# lightplayslider.net
KiCad netlist of a schematic drawn in EAGLE
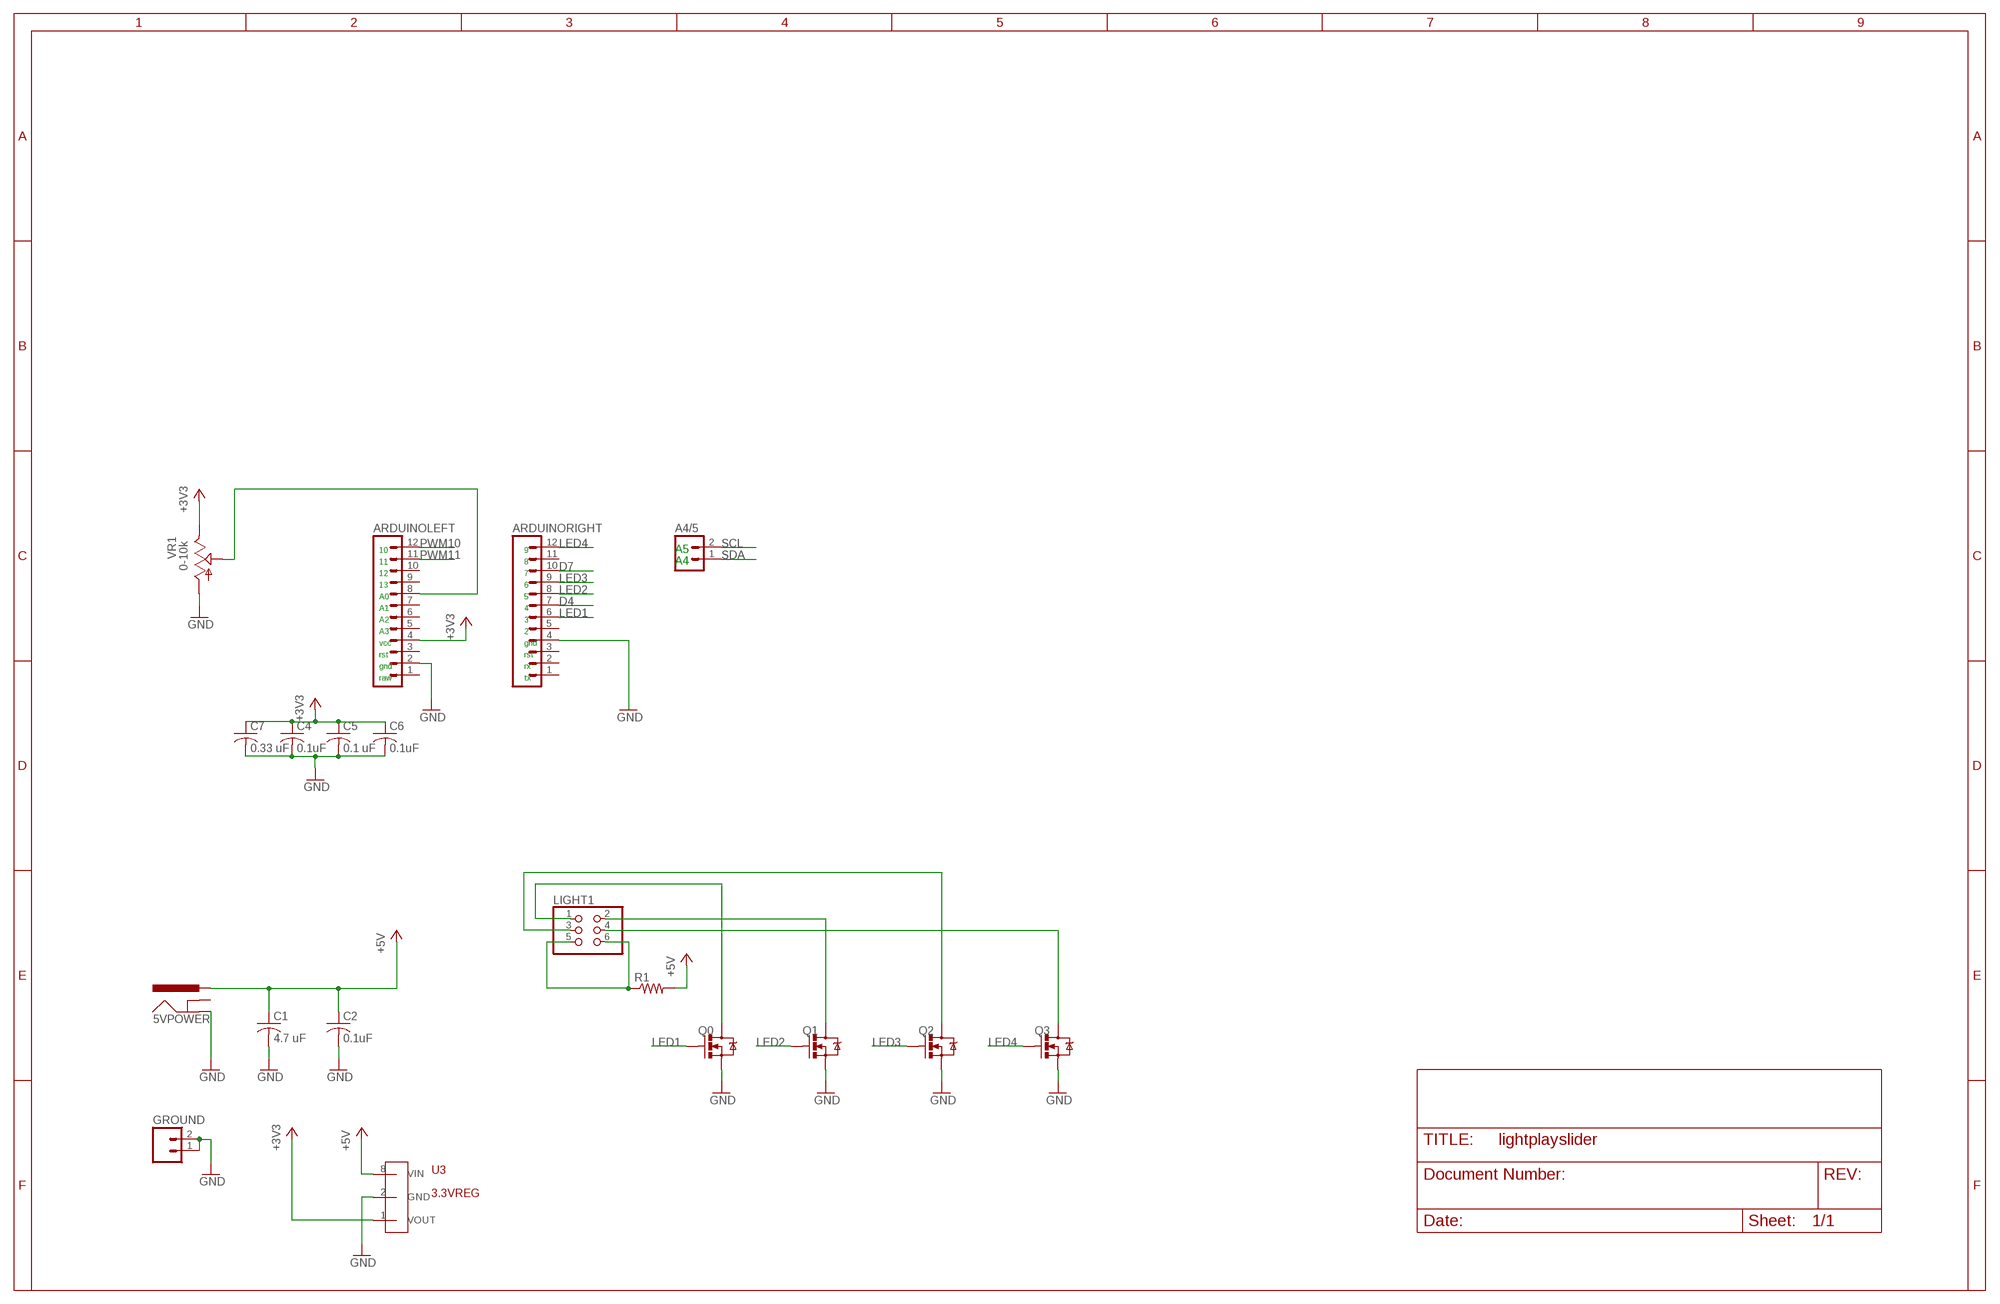
[diagram p0: schematic, sheet 1]

(export (version "E")
  (design (tool "Eeschema 10.0.6"))
  (components
    (comp (ref "5VPOWER")
      (value "POWER_JACKPTH")
      (footprint "eagle-import:POWER_JACK_PTH")
      (libsource (lib "eagle-import") (part "POWER_JACKPTH"))
    )
    (comp (ref "A4/5")
      (value "M02PTH")
      (footprint "eagle-import:1X02")
      (libsource (lib "eagle-import") (part "M02PTH"))
    )
    (comp (ref "ARDUINOLEFT")
      (value "M12PTH")
      (footprint "eagle-import:1X12")
      (libsource (lib "eagle-import") (part "M12PTH"))
    )
    (comp (ref "ARDUINORIGHT")
      (value "M12PTH")
      (footprint "eagle-import:1X12")
      (libsource (lib "eagle-import") (part "M12PTH"))
    )
    (comp (ref "C1")
      (value "4.7 uF")
      (footprint "eagle-import:C1206")
      (libsource (lib "eagle-import") (part "C-USC1206"))
    )
    (comp (ref "C2")
      (value "0.1uF")
      (footprint "eagle-import:C0805")
      (libsource (lib "eagle-import") (part "C-USC0805"))
    )
    (comp (ref "C4")
      (value "0.1uF")
      (footprint "eagle-import:C0805")
      (libsource (lib "eagle-import") (part "C-USC0805"))
    )
    (comp (ref "C5")
      (value "0.1 uF")
      (footprint "eagle-import:C0805")
      (libsource (lib "eagle-import") (part "C-USC0805"))
    )
    (comp (ref "C6")
      (value "0.1uF")
      (footprint "eagle-import:C0805")
      (libsource (lib "eagle-import") (part "C-USC0805"))
    )
    (comp (ref "C7")
      (value "0.33 uF")
      (footprint "eagle-import:C1206")
      (libsource (lib "eagle-import") (part "C-USC1206"))
    )
    (comp (ref "GROUND")
      (value "M02PTH")
      (footprint "eagle-import:1X02")
      (libsource (lib "eagle-import") (part "M02PTH"))
    )
    (comp (ref "LIGHT1")
      (value "PINHD-2X3")
      (footprint "eagle-import:2X03")
      (libsource (lib "eagle-import") (part "PINHD-2X3"))
    )
    (comp (ref "Q0")
      (value "MOSFET-NCHANNELAO3404A")
      (footprint "eagle-import:SOT23-3")
      (libsource (lib "eagle-import") (part "MOSFET-NCHANNELAO3404A"))
    )
    (comp (ref "Q1")
      (value "MOSFET-NCHANNELAO3404A")
      (footprint "eagle-import:SOT23-3")
      (libsource (lib "eagle-import") (part "MOSFET-NCHANNELAO3404A"))
    )
    (comp (ref "Q2")
      (value "MOSFET-NCHANNELAO3404A")
      (footprint "eagle-import:SOT23-3")
      (libsource (lib "eagle-import") (part "MOSFET-NCHANNELAO3404A"))
    )
    (comp (ref "Q3")
      (value "MOSFET-NCHANNELAO3404A")
      (footprint "eagle-import:SOT23-3")
      (libsource (lib "eagle-import") (part "MOSFET-NCHANNELAO3404A"))
    )
    (comp (ref "R1")
      (value "R-US_0617/17")
      (footprint "eagle-import:0617_17")
      (libsource (lib "eagle-import") (part "R-US_0617/17"))
    )
    (comp (ref "U3")
      (value "3.3VREG")
      (footprint "eagle-import:SO08")
      (libsource (lib "eagle-import") (part "STM3.3VREG"))
    )
    (comp (ref "VR1")
      (value "0-10k")
      (footprint "eagle-import:SLIDER-MEDIUM")
      (libsource (lib "eagle-import") (part "SLIDER30MM"))
    )
  )
  (nets
    (net (code "1") (name "+3V3") (class "Default")
      (node (ref "ARDUINOLEFT") (pin "4") (pinfunction "4_4") (pintype "passive"))
      (node (ref "C4") (pin "1") (pinfunction "1_1") (pintype "passive"))
      (node (ref "C5") (pin "1") (pinfunction "1_1") (pintype "passive"))
      (node (ref "C6") (pin "1") (pinfunction "1_1") (pintype "passive"))
      (node (ref "C7") (pin "1") (pinfunction "1_1") (pintype "passive"))
      (node (ref "U3") (pin "1") (pinfunction "VOUT_1") (pintype "bidirectional"))
      (node (ref "VR1") (pin "TOP") (pinfunction "E_TOP") (pintype "passive"))
    )
    (net (code "2") (name "+5V") (class "Default")
      (node (ref "5VPOWER") (pin "PWR") (pinfunction "PWR_PWR") (pintype "bidirectional"))
      (node (ref "C1") (pin "1") (pinfunction "1_1") (pintype "passive"))
      (node (ref "C2") (pin "1") (pinfunction "1_1") (pintype "passive"))
      (node (ref "R1") (pin "2") (pinfunction "2_2") (pintype "passive"))
      (node (ref "U3") (pin "8") (pinfunction "VIN_8") (pintype "bidirectional"))
    )
    (net (code "3") (name "/D4") (class "Default")
      (node (ref "ARDUINORIGHT") (pin "7") (pinfunction "7_7") (pintype "passive"))
    )
    (net (code "4") (name "/D7") (class "Default")
      (node (ref "ARDUINORIGHT") (pin "10") (pinfunction "10_10") (pintype "passive"))
    )
    (net (code "5") (name "/LED1") (class "Default")
      (node (ref "ARDUINORIGHT") (pin "6") (pinfunction "6_6") (pintype "passive"))
      (node (ref "Q0") (pin "1") (pinfunction "G_1") (pintype "passive"))
    )
    (net (code "6") (name "/LED2") (class "Default")
      (node (ref "ARDUINORIGHT") (pin "8") (pinfunction "8_8") (pintype "passive"))
      (node (ref "Q1") (pin "1") (pinfunction "G_1") (pintype "passive"))
    )
    (net (code "7") (name "/LED3") (class "Default")
      (node (ref "ARDUINORIGHT") (pin "9") (pinfunction "9_9") (pintype "passive"))
      (node (ref "Q2") (pin "1") (pinfunction "G_1") (pintype "passive"))
    )
    (net (code "8") (name "/LED4") (class "Default")
      (node (ref "ARDUINORIGHT") (pin "12") (pinfunction "12_12") (pintype "passive"))
      (node (ref "Q3") (pin "1") (pinfunction "G_1") (pintype "passive"))
    )
    (net (code "9") (name "/PWM10") (class "Default")
      (node (ref "ARDUINOLEFT") (pin "12") (pinfunction "12_12") (pintype "passive"))
    )
    (net (code "10") (name "/PWM11") (class "Default")
      (node (ref "ARDUINOLEFT") (pin "11") (pinfunction "11_11") (pintype "passive"))
    )
    (net (code "11") (name "/SCL") (class "Default")
      (node (ref "A4/5") (pin "2") (pinfunction "2_2") (pintype "passive"))
    )
    (net (code "12") (name "/SDA") (class "Default")
      (node (ref "A4/5") (pin "1") (pinfunction "1_1") (pintype "passive"))
    )
    (net (code "13") (name "GND") (class "Default")
      (node (ref "5VPOWER") (pin "GND") (pinfunction "GND_GND") (pintype "bidirectional"))
      (node (ref "ARDUINOLEFT") (pin "2") (pinfunction "2_2") (pintype "passive"))
      (node (ref "ARDUINORIGHT") (pin "4") (pinfunction "4_4") (pintype "passive"))
      (node (ref "C1") (pin "2") (pinfunction "2_2") (pintype "passive"))
      (node (ref "C2") (pin "2") (pinfunction "2_2") (pintype "passive"))
      (node (ref "C4") (pin "2") (pinfunction "2_2") (pintype "passive"))
      (node (ref "C5") (pin "2") (pinfunction "2_2") (pintype "passive"))
      (node (ref "C6") (pin "2") (pinfunction "2_2") (pintype "passive"))
      (node (ref "C7") (pin "2") (pinfunction "2_2") (pintype "passive"))
      (node (ref "GROUND") (pin "1") (pinfunction "1_1") (pintype "passive"))
      (node (ref "GROUND") (pin "2") (pinfunction "2_2") (pintype "passive"))
      (node (ref "Q0") (pin "2") (pinfunction "S_2") (pintype "passive"))
      (node (ref "Q1") (pin "2") (pinfunction "S_2") (pintype "passive"))
      (node (ref "Q2") (pin "2") (pinfunction "S_2") (pintype "passive"))
      (node (ref "Q3") (pin "2") (pinfunction "S_2") (pintype "passive"))
      (node (ref "U3") (pin "2") (pinfunction "GND_2") (pintype "bidirectional"))
      (node (ref "VR1") (pin "BOTTOM") (pinfunction "A_BOTTOM") (pintype "passive"))
    )
    (net (code "14") (name "Net-(LIGHT1-Pad5)") (class "Default")
      (node (ref "LIGHT1") (pin "5") (pinfunction "5_5") (pintype "passive"))
      (node (ref "LIGHT1") (pin "6") (pinfunction "6_6") (pintype "passive"))
      (node (ref "R1") (pin "1") (pinfunction "1_1") (pintype "passive"))
    )
    (net (code "15") (name "Net-(Q0-D)") (class "Default")
      (node (ref "LIGHT1") (pin "1") (pinfunction "1_1") (pintype "passive"))
      (node (ref "Q0") (pin "3") (pinfunction "D_3") (pintype "passive"))
    )
    (net (code "16") (name "Net-(Q1-D)") (class "Default")
      (node (ref "LIGHT1") (pin "2") (pinfunction "2_2") (pintype "passive"))
      (node (ref "Q1") (pin "3") (pinfunction "D_3") (pintype "passive"))
    )
    (net (code "17") (name "Net-(Q2-D)") (class "Default")
      (node (ref "LIGHT1") (pin "3") (pinfunction "3_3") (pintype "passive"))
      (node (ref "Q2") (pin "3") (pinfunction "D_3") (pintype "passive"))
    )
    (net (code "18") (name "Net-(Q3-D)") (class "Default")
      (node (ref "LIGHT1") (pin "4") (pinfunction "4_4") (pintype "passive"))
      (node (ref "Q3") (pin "3") (pinfunction "D_3") (pintype "passive"))
    )
    (net (code "19") (name "Net-(VR1-S)") (class "Default")
      (node (ref "ARDUINOLEFT") (pin "8") (pinfunction "8_8") (pintype "passive"))
      (node (ref "VR1") (pin "WIPER") (pinfunction "S_WIPER") (pintype "passive"))
    )
    (net (code "20") (name "unconnected-(5VPOWER-PadGNDBREAK)") (class "Default")
      (node (ref "5VPOWER") (pin "GNDBREAK") (pinfunction "GNDBREAK_GNDBREAK") (pintype "bidirectional"))
    )
    (net (code "21") (name "unconnected-(ARDUINOLEFT-Pad1)") (class "Default")
      (node (ref "ARDUINOLEFT") (pin "1") (pinfunction "1_1") (pintype "passive"))
    )
    (net (code "22") (name "unconnected-(ARDUINOLEFT-Pad3)") (class "Default")
      (node (ref "ARDUINOLEFT") (pin "3") (pinfunction "3_3") (pintype "passive"))
    )
    (net (code "23") (name "unconnected-(ARDUINOLEFT-Pad5)") (class "Default")
      (node (ref "ARDUINOLEFT") (pin "5") (pinfunction "5_5") (pintype "passive"))
    )
    (net (code "24") (name "unconnected-(ARDUINOLEFT-Pad6)") (class "Default")
      (node (ref "ARDUINOLEFT") (pin "6") (pinfunction "6_6") (pintype "passive"))
    )
    (net (code "25") (name "unconnected-(ARDUINOLEFT-Pad7)") (class "Default")
      (node (ref "ARDUINOLEFT") (pin "7") (pinfunction "7_7") (pintype "passive"))
    )
    (net (code "26") (name "unconnected-(ARDUINOLEFT-Pad9)") (class "Default")
      (node (ref "ARDUINOLEFT") (pin "9") (pinfunction "9_9") (pintype "passive"))
    )
    (net (code "27") (name "unconnected-(ARDUINOLEFT-Pad10)") (class "Default")
      (node (ref "ARDUINOLEFT") (pin "10") (pinfunction "10_10") (pintype "passive"))
    )
    (net (code "28") (name "unconnected-(ARDUINORIGHT-Pad1)") (class "Default")
      (node (ref "ARDUINORIGHT") (pin "1") (pinfunction "1_1") (pintype "passive"))
    )
    (net (code "29") (name "unconnected-(ARDUINORIGHT-Pad2)") (class "Default")
      (node (ref "ARDUINORIGHT") (pin "2") (pinfunction "2_2") (pintype "passive"))
    )
    (net (code "30") (name "unconnected-(ARDUINORIGHT-Pad3)") (class "Default")
      (node (ref "ARDUINORIGHT") (pin "3") (pinfunction "3_3") (pintype "passive"))
    )
    (net (code "31") (name "unconnected-(ARDUINORIGHT-Pad5)") (class "Default")
      (node (ref "ARDUINORIGHT") (pin "5") (pinfunction "5_5") (pintype "passive"))
    )
    (net (code "32") (name "unconnected-(ARDUINORIGHT-Pad11)") (class "Default")
      (node (ref "ARDUINORIGHT") (pin "11") (pinfunction "11_11") (pintype "passive"))
    )
  )
)
